# TempestShockerUpper_V2.net
KiCad netlist of a schematic drawn in EAGLE
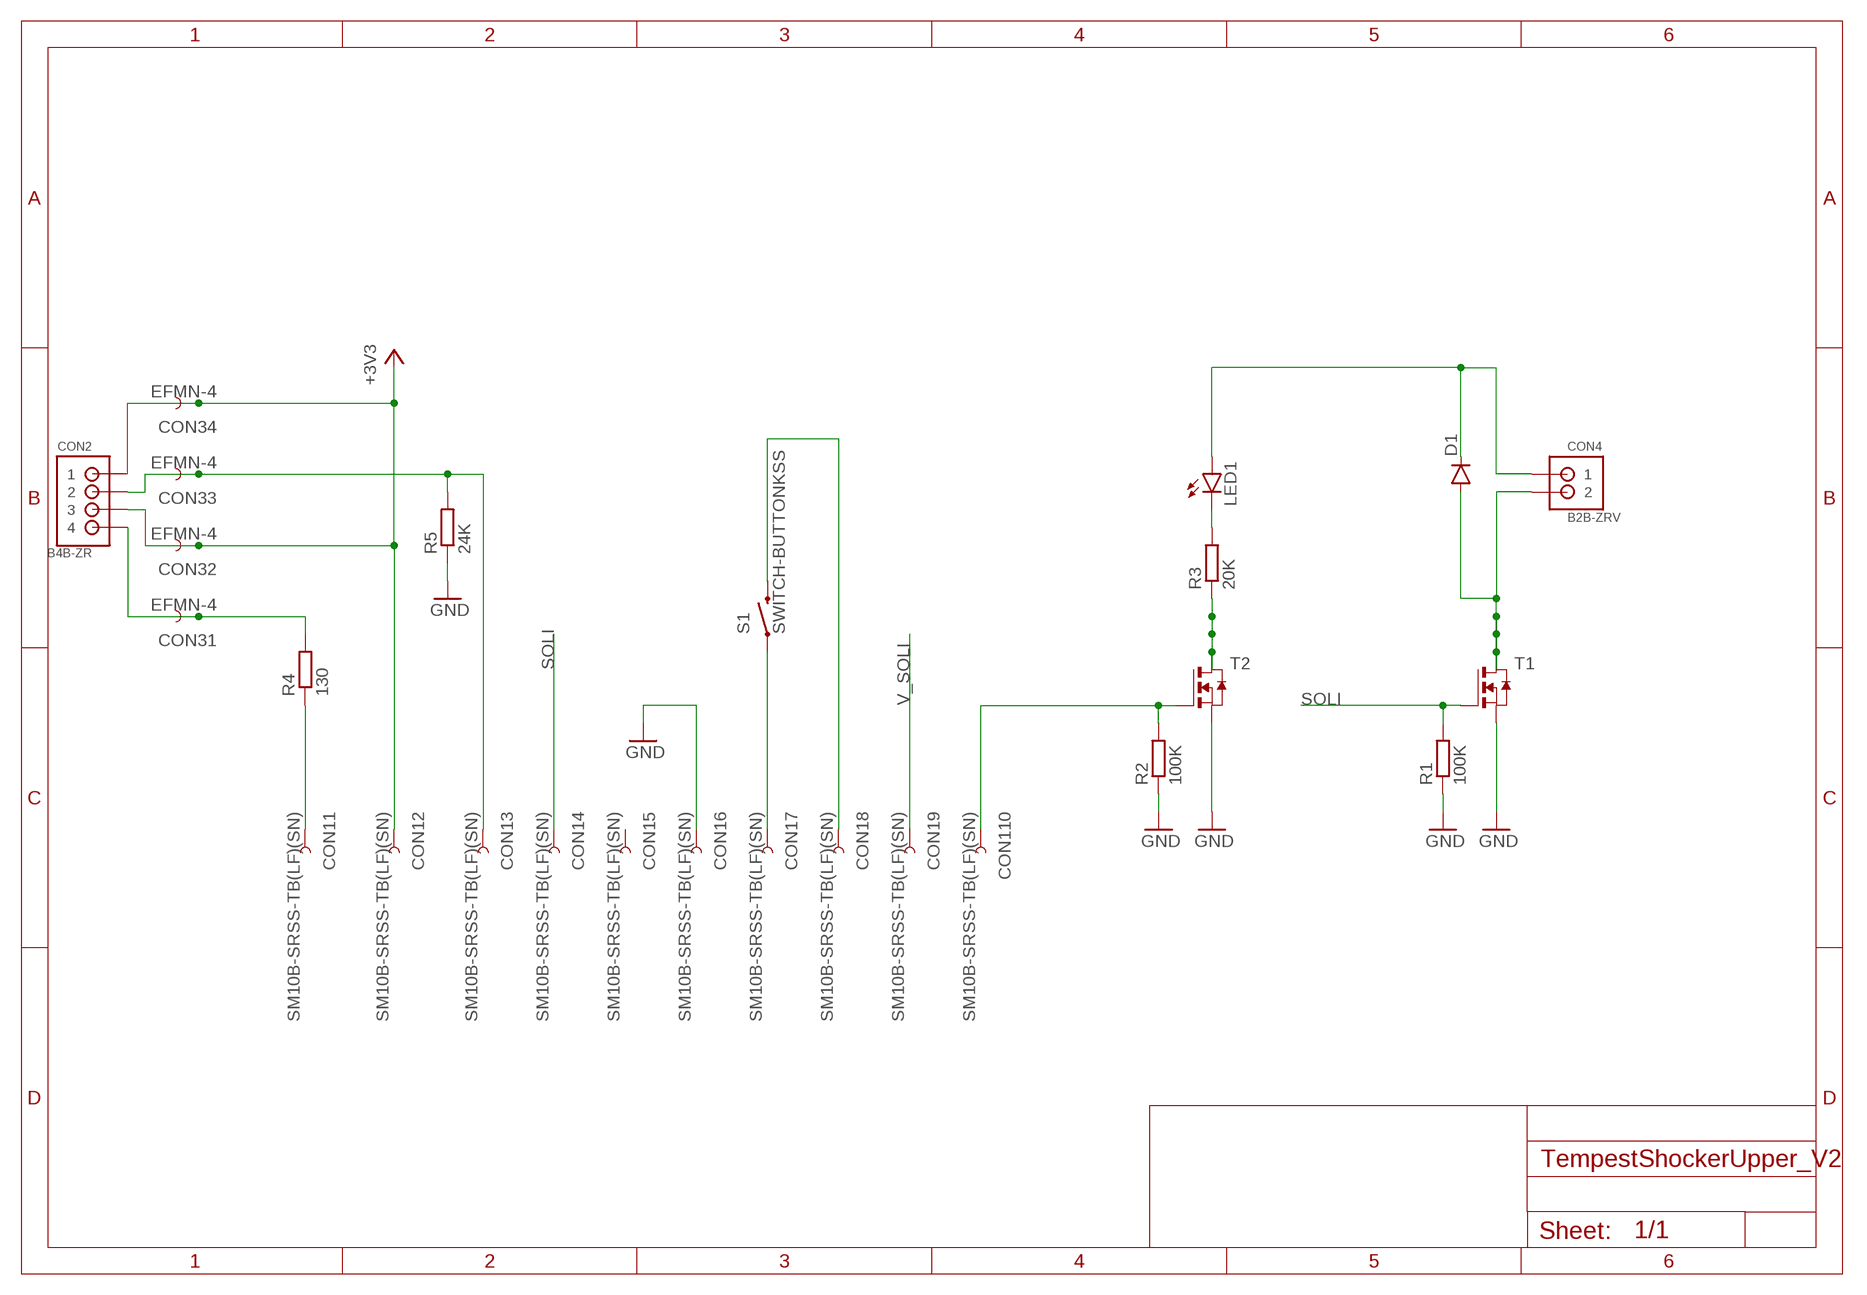
[diagram p0: schematic, sheet 1]

(export (version "E")
  (design (tool "Eeschema 10.0.6"))
  (components
    (comp (ref "CON1")
      (value "SM10B-SRSS-TB(LF)(SN)")
      (footprint "eagle-import:SM10B-SRSS-TB")
      (libsource (lib "eagle-import") (part "SM10B-SRSS-TB(LF)(SN)"))
    )
    (comp (ref "CON2")
      (value "B4B-ZR")
      (footprint "eagle-import:S4B-ZR")
      (libsource (lib "eagle-import") (part "B4B-ZR"))
    )
    (comp (ref "CON3")
      (value "EFMN-4")
      (footprint "eagle-import:EFMN-4")
      (libsource (lib "eagle-import") (part "EFMN-4"))
    )
    (comp (ref "CON4")
      (value "B2B-ZRV")
      (footprint "eagle-import:S2B-ZR-VERT")
      (libsource (lib "eagle-import") (part "B2B-ZRV"))
    )
    (comp (ref "D1")
      (value "DIODE-SSOD123")
      (footprint "eagle-import:SOD-123")
      (libsource (lib "eagle-import") (part "DIODE-SSOD123"))
    )
    (comp (ref "LED1")
      (value "LED0603")
      (footprint "eagle-import:LED-0603")
      (libsource (lib "eagle-import") (part "LED0603"))
    )
    (comp (ref "R1")
      (value "100K")
      (footprint "eagle-import:_0603MP")
      (libsource (lib "eagle-import") (part "R0603"))
    )
    (comp (ref "R2")
      (value "100K")
      (footprint "eagle-import:_0603MP")
      (libsource (lib "eagle-import") (part "R0603"))
    )
    (comp (ref "R3")
      (value "20K")
      (footprint "eagle-import:_0603MP")
      (libsource (lib "eagle-import") (part "R0603"))
    )
    (comp (ref "R4")
      (value "130")
      (footprint "eagle-import:_0603MP")
      (libsource (lib "eagle-import") (part "R0603"))
    )
    (comp (ref "R5")
      (value "24K")
      (footprint "eagle-import:_0603MP")
      (libsource (lib "eagle-import") (part "R0603"))
    )
    (comp (ref "S1")
      (value "SWITCH-BUTTONKSS")
      (footprint "eagle-import:KSS")
      (libsource (lib "eagle-import") (part "SWITCH-BUTTONKSS"))
    )
    (comp (ref "T1")
      (value "NMOSSOT23-6")
      (footprint "eagle-import:SOT23-6")
      (libsource (lib "eagle-import") (part "NMOSSOT23-6"))
    )
    (comp (ref "T2")
      (value "NMOSSOT23-6")
      (footprint "eagle-import:SOT23-6")
      (libsource (lib "eagle-import") (part "NMOSSOT23-6"))
    )
  )
  (nets
    (net (code "1") (name "+3V3") (class "Default")
      (node (ref "CON1") (pin "2") (pinfunction "1_2") (pintype "bidirectional"))
      (node (ref "CON2") (pin "1") (pinfunction "1_1") (pintype "bidirectional"))
      (node (ref "CON2") (pin "3") (pinfunction "3_3") (pintype "bidirectional"))
      (node (ref "CON3") (pin "2") (pinfunction "1_2") (pintype "bidirectional"))
      (node (ref "CON3") (pin "4") (pinfunction "1_4") (pintype "bidirectional"))
    )
    (net (code "2") (name "/SOLI") (class "Default")
      (node (ref "CON1") (pin "4") (pinfunction "1_4") (pintype "bidirectional"))
      (node (ref "R1") (pin "2") (pinfunction "2_2") (pintype "passive"))
      (node (ref "T1") (pin "3") (pinfunction "G_3") (pintype "passive"))
    )
    (net (code "3") (name "/V_SOLI") (class "Default")
      (node (ref "CON1") (pin "9") (pinfunction "1_9") (pintype "bidirectional"))
      (node (ref "CON4") (pin "1") (pinfunction "1_1") (pintype "bidirectional"))
      (node (ref "D1") (pin "C") (pinfunction "C_C") (pintype "passive"))
      (node (ref "LED1") (pin "A") (pinfunction "A_A") (pintype "passive"))
    )
    (net (code "4") (name "GND") (class "Default")
      (node (ref "CON1") (pin "6") (pinfunction "1_6") (pintype "bidirectional"))
      (node (ref "R1") (pin "1") (pinfunction "1_1") (pintype "passive"))
      (node (ref "R2") (pin "1") (pinfunction "1_1") (pintype "passive"))
      (node (ref "R5") (pin "1") (pinfunction "1_1") (pintype "passive"))
      (node (ref "T1") (pin "4") (pinfunction "S_4") (pintype "passive"))
      (node (ref "T2") (pin "4") (pinfunction "S_4") (pintype "passive"))
    )
    (net (code "5") (name "Net-(CON1-Pad1)") (class "Default")
      (node (ref "CON1") (pin "1") (pinfunction "1_1") (pintype "bidirectional"))
      (node (ref "R4") (pin "1") (pinfunction "1_1") (pintype "passive"))
    )
    (net (code "6") (name "Net-(CON1B-1)") (class "Default")
      (node (ref "CON1") (pin "10") (pinfunction "1_10") (pintype "bidirectional"))
      (node (ref "R2") (pin "2") (pinfunction "2_2") (pintype "passive"))
      (node (ref "T2") (pin "3") (pinfunction "G_3") (pintype "passive"))
    )
    (net (code "7") (name "Net-(CON1D-1)") (class "Default")
      (node (ref "CON1") (pin "3") (pinfunction "1_3") (pintype "bidirectional"))
      (node (ref "CON2") (pin "2") (pinfunction "2_2") (pintype "bidirectional"))
      (node (ref "CON3") (pin "3") (pinfunction "1_3") (pintype "bidirectional"))
      (node (ref "R5") (pin "2") (pinfunction "2_2") (pintype "passive"))
    )
    (net (code "8") (name "Net-(CON1H-1)") (class "Default")
      (node (ref "CON1") (pin "7") (pinfunction "1_7") (pintype "bidirectional"))
      (node (ref "S1") (pin "1") (pinfunction "1_1") (pintype "passive"))
    )
    (net (code "9") (name "Net-(CON1I-1)") (class "Default")
      (node (ref "CON1") (pin "8") (pinfunction "1_8") (pintype "bidirectional"))
      (node (ref "S1") (pin "2") (pinfunction "2_2") (pintype "passive"))
    )
    (net (code "10") (name "Net-(CON2-Pad4)") (class "Default")
      (node (ref "CON2") (pin "4") (pinfunction "4_4") (pintype "bidirectional"))
      (node (ref "CON3") (pin "1") (pinfunction "1_1") (pintype "bidirectional"))
      (node (ref "R4") (pin "2") (pinfunction "2_2") (pintype "passive"))
    )
    (net (code "11") (name "Net-(LED1-PadC)") (class "Default")
      (node (ref "LED1") (pin "C") (pinfunction "C_C") (pintype "passive"))
      (node (ref "R3") (pin "2") (pinfunction "2_2") (pintype "passive"))
    )
    (net (code "12") (name "Net-(T1-D)") (class "Default")
      (node (ref "CON4") (pin "2") (pinfunction "2_2") (pintype "bidirectional"))
      (node (ref "D1") (pin "A") (pinfunction "A_A") (pintype "passive"))
      (node (ref "T1") (pin "1") (pinfunction "D_1") (pintype "passive"))
      (node (ref "T1") (pin "2") (pinfunction "D1_2") (pintype "passive"))
      (node (ref "T1") (pin "5") (pinfunction "D2_5") (pintype "passive"))
      (node (ref "T1") (pin "6") (pinfunction "D3_6") (pintype "passive"))
    )
    (net (code "13") (name "Net-(T2-D)") (class "Default")
      (node (ref "R3") (pin "1") (pinfunction "1_1") (pintype "passive"))
      (node (ref "T2") (pin "1") (pinfunction "D_1") (pintype "passive"))
      (node (ref "T2") (pin "2") (pinfunction "D1_2") (pintype "passive"))
      (node (ref "T2") (pin "5") (pinfunction "D2_5") (pintype "passive"))
      (node (ref "T2") (pin "6") (pinfunction "D3_6") (pintype "passive"))
    )
    (net (code "14") (name "unconnected-(CON1F-1-Pad5)") (class "Default")
      (node (ref "CON1") (pin "5") (pinfunction "1_5") (pintype "bidirectional"))
    )
  )
)
